# millSensorBoard.net
KiCad netlist of a schematic drawn in EAGLE
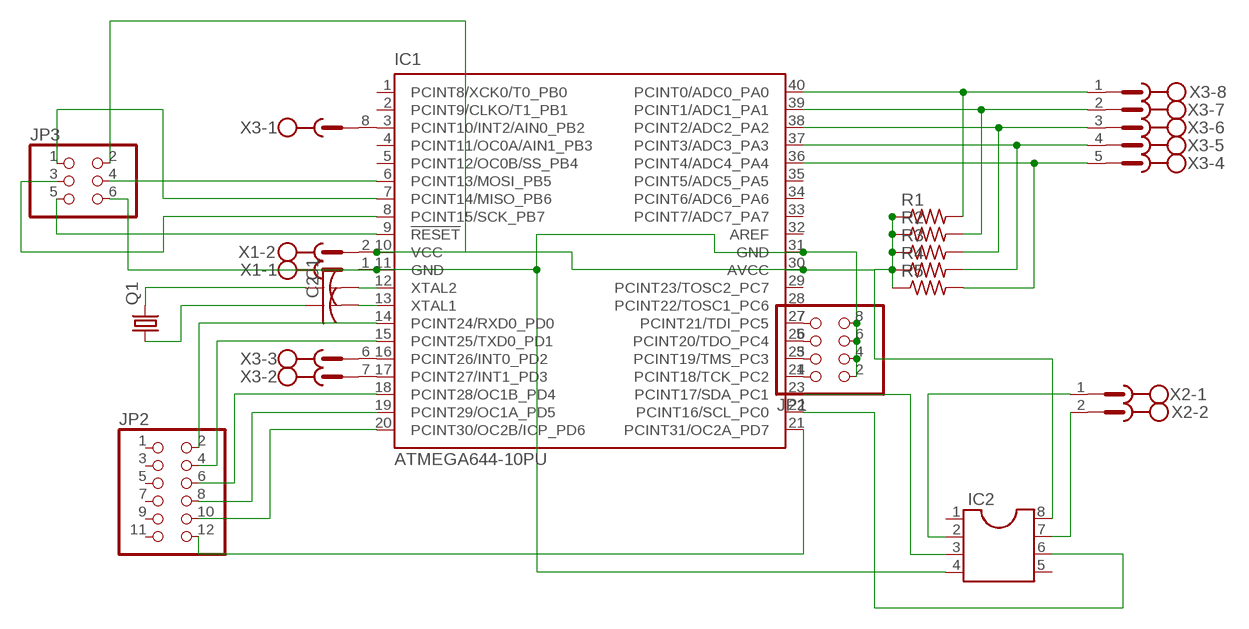
[diagram p0: schematic, sheet 1]

(export (version "E")
  (design (tool "Eeschema 10.0.6"))
  (components
    (comp (ref "C1")
      (value "C-US025-025X050")
      (footprint "eagle-import:C025-025X050")
      (libsource (lib "eagle-import") (part "C-US025-025X050"))
    )
    (comp (ref "C2")
      (value "C-US025-025X050")
      (footprint "eagle-import:C025-025X050")
      (libsource (lib "eagle-import") (part "C-US025-025X050"))
    )
    (comp (ref "IC1")
      (value "ATMEGA644-10PU")
      (footprint "eagle-import:DIL40")
      (fields (field (name "MPN") "ATMEGA644V-10PU"))
      (libsource (lib "eagle-import") (part "ATMEGA644-PU10"))
    )
    (comp (ref "IC2")
      (value "DIL8")
      (footprint "eagle-import:DIL08")
      (libsource (lib "eagle-import") (part "DIL8"))
    )
    (comp (ref "JP1")
      (value "PINHD-2X4")
      (footprint "eagle-import:2X04")
      (libsource (lib "eagle-import") (part "PINHD-2X4"))
    )
    (comp (ref "JP2")
      (value "PINHD-2X6")
      (footprint "eagle-import:2X06")
      (libsource (lib "eagle-import") (part "PINHD-2X6"))
    )
    (comp (ref "JP3")
      (value "PINHD-2X3")
      (footprint "eagle-import:2X03")
      (libsource (lib "eagle-import") (part "PINHD-2X3"))
    )
    (comp (ref "Q1")
      (value "CRYSTALHC49S")
      (footprint "eagle-import:HC49_S")
      (libsource (lib "eagle-import") (part "CRYSTALHC49S"))
    )
    (comp (ref "R1")
      (value "R-US_0207/10")
      (footprint "eagle-import:0207_10")
      (libsource (lib "eagle-import") (part "R-US_0207/10"))
    )
    (comp (ref "R2")
      (value "R-US_0207/10")
      (footprint "eagle-import:0207_10")
      (libsource (lib "eagle-import") (part "R-US_0207/10"))
    )
    (comp (ref "R3")
      (value "R-US_0207/10")
      (footprint "eagle-import:0207_10")
      (libsource (lib "eagle-import") (part "R-US_0207/10"))
    )
    (comp (ref "R4")
      (value "R-US_0207/10")
      (footprint "eagle-import:0207_10")
      (libsource (lib "eagle-import") (part "R-US_0207/10"))
    )
    (comp (ref "R5")
      (value "R-US_0207/10")
      (footprint "eagle-import:0207_10")
      (libsource (lib "eagle-import") (part "R-US_0207/10"))
    )
    (comp (ref "X1")
      (value "MSTBV2")
      (footprint "eagle-import:MSTBV2")
      (libsource (lib "eagle-import") (part "MSTBV2"))
    )
    (comp (ref "X2")
      (value "MSTBV2")
      (footprint "eagle-import:MSTBV2")
      (libsource (lib "eagle-import") (part "MSTBV2"))
    )
    (comp (ref "X3")
      (value "MSTBV8")
      (footprint "eagle-import:MSTBV8")
      (libsource (lib "eagle-import") (part "MSTBV8"))
    )
  )
  (nets
    (net (code "1") (name "Net-(C1-Pad1)") (class "Default")
      (node (ref "C1") (pin "1") (pinfunction "1_1") (pintype "passive"))
      (node (ref "Q1") (pin "2") (pinfunction "2_2") (pintype "passive"))
    )
    (net (code "2") (name "Net-(C2-Pad1)") (class "Default")
      (node (ref "C2") (pin "1") (pinfunction "1_1") (pintype "passive"))
      (node (ref "Q1") (pin "1") (pinfunction "1_1") (pintype "passive"))
    )
    (net (code "3") (name "Net-(IC1-AVCC)") (class "Default")
      (node (ref "IC1") (pin "10") (pinfunction "VCC_10") (pintype "power_in"))
      (node (ref "IC1") (pin "30") (pinfunction "AVCC_30") (pintype "power_in"))
      (node (ref "IC2") (pin "8") (pinfunction "8_8") (pintype "passive"))
      (node (ref "JP3") (pin "2") (pinfunction "2_2") (pintype "passive"))
      (node (ref "R1") (pin "1") (pinfunction "1_1") (pintype "passive"))
      (node (ref "R2") (pin "1") (pinfunction "1_1") (pintype "passive"))
      (node (ref "R3") (pin "1") (pinfunction "1_1") (pintype "passive"))
      (node (ref "R4") (pin "1") (pinfunction "1_1") (pintype "passive"))
      (node (ref "R5") (pin "1") (pinfunction "1_1") (pintype "passive"))
      (node (ref "X1") (pin "2") (pinfunction "SK_2") (pintype "passive"))
    )
    (net (code "4") (name "Net-(IC1-PCINT0{slash}ADC0_PA0)") (class "Default")
      (node (ref "IC1") (pin "40") (pinfunction "PCINT0/ADC0_PA0_40") (pintype "bidirectional"))
      (node (ref "R1") (pin "2") (pinfunction "2_2") (pintype "passive"))
      (node (ref "X3") (pin "1") (pinfunction "SK_1") (pintype "passive"))
    )
    (net (code "5") (name "Net-(IC1-PCINT1{slash}ADC1_PA1)") (class "Default")
      (node (ref "IC1") (pin "39") (pinfunction "PCINT1/ADC1_PA1_39") (pintype "bidirectional"))
      (node (ref "R2") (pin "2") (pinfunction "2_2") (pintype "passive"))
      (node (ref "X3") (pin "2") (pinfunction "SK_2") (pintype "passive"))
    )
    (net (code "6") (name "Net-(IC1-PCINT2{slash}ADC2_PA2)") (class "Default")
      (node (ref "IC1") (pin "38") (pinfunction "PCINT2/ADC2_PA2_38") (pintype "bidirectional"))
      (node (ref "R3") (pin "2") (pinfunction "2_2") (pintype "passive"))
      (node (ref "X3") (pin "3") (pinfunction "SK_3") (pintype "passive"))
    )
    (net (code "7") (name "Net-(IC1-PCINT3{slash}ADC3_PA3)") (class "Default")
      (node (ref "IC1") (pin "37") (pinfunction "PCINT3/ADC3_PA3_37") (pintype "bidirectional"))
      (node (ref "R4") (pin "2") (pinfunction "2_2") (pintype "passive"))
      (node (ref "X3") (pin "4") (pinfunction "SK_4") (pintype "passive"))
    )
    (net (code "8") (name "Net-(IC1-PCINT4{slash}ADC4_PA4)") (class "Default")
      (node (ref "IC1") (pin "36") (pinfunction "PCINT4/ADC4_PA4_36") (pintype "bidirectional"))
      (node (ref "R5") (pin "2") (pinfunction "2_2") (pintype "passive"))
      (node (ref "X3") (pin "5") (pinfunction "SK_5") (pintype "passive"))
    )
    (net (code "9") (name "Net-(IC1-PCINT10{slash}INT2{slash}AIN0_PB2)") (class "Default")
      (node (ref "IC1") (pin "3") (pinfunction "PCINT10/INT2/AIN0_PB2_3") (pintype "bidirectional"))
      (node (ref "X3") (pin "8") (pinfunction "SK_8") (pintype "passive"))
    )
    (net (code "10") (name "Net-(IC1-PCINT13{slash}MOSI_PB5)") (class "Default")
      (node (ref "IC1") (pin "6") (pinfunction "PCINT13/MOSI_PB5_6") (pintype "bidirectional"))
      (node (ref "JP3") (pin "4") (pinfunction "4_4") (pintype "passive"))
    )
    (net (code "11") (name "Net-(IC1-PCINT14{slash}MISO_PB6)") (class "Default")
      (node (ref "IC1") (pin "7") (pinfunction "PCINT14/MISO_PB6_7") (pintype "bidirectional"))
      (node (ref "JP3") (pin "1") (pinfunction "1_1") (pintype "passive"))
    )
    (net (code "12") (name "Net-(IC1-PCINT15{slash}SCK_PB7)") (class "Default")
      (node (ref "IC1") (pin "8") (pinfunction "PCINT15/SCK_PB7_8") (pintype "bidirectional"))
      (node (ref "JP3") (pin "3") (pinfunction "3_3") (pintype "passive"))
    )
    (net (code "13") (name "Net-(IC1-PCINT16{slash}SCL_PC0)") (class "Default")
      (node (ref "IC1") (pin "22") (pinfunction "PCINT16/SCL_PC0_22") (pintype "bidirectional"))
      (node (ref "IC2") (pin "6") (pinfunction "6_6") (pintype "passive"))
    )
    (net (code "14") (name "Net-(IC1-PCINT17{slash}SDA_PC1)") (class "Default")
      (node (ref "IC1") (pin "23") (pinfunction "PCINT17/SDA_PC1_23") (pintype "bidirectional"))
      (node (ref "IC2") (pin "3") (pinfunction "3_3") (pintype "passive"))
    )
    (net (code "15") (name "Net-(IC1-PCINT18{slash}TCK_PC2)") (class "Default")
      (node (ref "IC1") (pin "24") (pinfunction "PCINT18/TCK_PC2_24") (pintype "bidirectional"))
      (node (ref "JP1") (pin "1") (pinfunction "1_1") (pintype "passive"))
    )
    (net (code "16") (name "Net-(IC1-PCINT19{slash}TMS_PC3)") (class "Default")
      (node (ref "IC1") (pin "25") (pinfunction "PCINT19/TMS_PC3_25") (pintype "bidirectional"))
      (node (ref "JP1") (pin "3") (pinfunction "3_3") (pintype "passive"))
    )
    (net (code "17") (name "Net-(IC1-PCINT20{slash}TDO_PC4)") (class "Default")
      (node (ref "IC1") (pin "26") (pinfunction "PCINT20/TDO_PC4_26") (pintype "bidirectional"))
      (node (ref "JP1") (pin "5") (pinfunction "5_5") (pintype "passive"))
    )
    (net (code "18") (name "Net-(IC1-PCINT21{slash}TDI_PC5)") (class "Default")
      (node (ref "IC1") (pin "27") (pinfunction "PCINT21/TDI_PC5_27") (pintype "bidirectional"))
      (node (ref "JP1") (pin "7") (pinfunction "7_7") (pintype "passive"))
    )
    (net (code "19") (name "Net-(IC1-PCINT24{slash}RXD0_PD0)") (class "Default")
      (node (ref "IC1") (pin "14") (pinfunction "PCINT24/RXD0_PD0_14") (pintype "bidirectional"))
      (node (ref "JP2") (pin "2") (pinfunction "2_2") (pintype "passive"))
    )
    (net (code "20") (name "Net-(IC1-PCINT25{slash}TXD0_PD1)") (class "Default")
      (node (ref "IC1") (pin "15") (pinfunction "PCINT25/TXD0_PD1_15") (pintype "bidirectional"))
      (node (ref "JP2") (pin "4") (pinfunction "4_4") (pintype "passive"))
    )
    (net (code "21") (name "Net-(IC1-PCINT26{slash}INT0_PD2)") (class "Default")
      (node (ref "IC1") (pin "16") (pinfunction "PCINT26/INT0_PD2_16") (pintype "bidirectional"))
      (node (ref "X3") (pin "6") (pinfunction "SK_6") (pintype "passive"))
    )
    (net (code "22") (name "Net-(IC1-PCINT27{slash}INT1_PD3)") (class "Default")
      (node (ref "IC1") (pin "17") (pinfunction "PCINT27/INT1_PD3_17") (pintype "bidirectional"))
      (node (ref "X3") (pin "7") (pinfunction "SK_7") (pintype "passive"))
    )
    (net (code "23") (name "Net-(IC1-PCINT28{slash}OC1B_PD4)") (class "Default")
      (node (ref "IC1") (pin "18") (pinfunction "PCINT28/OC1B_PD4_18") (pintype "bidirectional"))
      (node (ref "JP2") (pin "6") (pinfunction "6_6") (pintype "passive"))
    )
    (net (code "24") (name "Net-(IC1-PCINT29{slash}OC1A_PD5)") (class "Default")
      (node (ref "IC1") (pin "19") (pinfunction "PCINT29/OC1A_PD5_19") (pintype "bidirectional"))
      (node (ref "JP2") (pin "8") (pinfunction "8_8") (pintype "passive"))
    )
    (net (code "25") (name "Net-(IC1-PCINT30{slash}OC2B{slash}ICP_PD6)") (class "Default")
      (node (ref "IC1") (pin "20") (pinfunction "PCINT30/OC2B/ICP_PD6_20") (pintype "bidirectional"))
      (node (ref "JP2") (pin "10") (pinfunction "10_10") (pintype "passive"))
    )
    (net (code "26") (name "Net-(IC1-PCINT31{slash}OC2A_PD7)") (class "Default")
      (node (ref "IC1") (pin "21") (pinfunction "PCINT31/OC2A_PD7_21") (pintype "bidirectional"))
      (node (ref "JP2") (pin "12") (pinfunction "12_12") (pintype "passive"))
    )
    (net (code "27") (name "Net-(IC1-XTAL1)") (class "Default")
      (node (ref "C2") (pin "2") (pinfunction "2_2") (pintype "passive"))
      (node (ref "IC1") (pin "13") (pinfunction "XTAL1_13") (pintype "input"))
    )
    (net (code "28") (name "Net-(IC1-XTAL2)") (class "Default")
      (node (ref "C1") (pin "2") (pinfunction "2_2") (pintype "passive"))
      (node (ref "IC1") (pin "12") (pinfunction "XTAL2_12") (pintype "output"))
    )
    (net (code "29") (name "Net-(IC1-~{RESET})") (class "Default")
      (node (ref "IC1") (pin "9") (pinfunction "~{RESET}_9") (pintype "input"))
      (node (ref "JP3") (pin "5") (pinfunction "5_5") (pintype "passive"))
    )
    (net (code "30") (name "Net-(X1A-SK)") (class "Default")
      (node (ref "IC1") (pin "11") (pinfunction "GND_11") (pintype "power_in"))
      (node (ref "IC1") (pin "31") (pinfunction "GND_31") (pintype "power_in"))
      (node (ref "IC2") (pin "4") (pinfunction "4_4") (pintype "passive"))
      (node (ref "JP1") (pin "2") (pinfunction "2_2") (pintype "passive"))
      (node (ref "JP1") (pin "4") (pinfunction "4_4") (pintype "passive"))
      (node (ref "JP1") (pin "6") (pinfunction "6_6") (pintype "passive"))
      (node (ref "JP1") (pin "8") (pinfunction "8_8") (pintype "passive"))
      (node (ref "JP3") (pin "6") (pinfunction "6_6") (pintype "passive"))
      (node (ref "X1") (pin "1") (pinfunction "SK_1") (pintype "passive"))
    )
    (net (code "31") (name "Net-(X2A-SK)") (class "Default")
      (node (ref "IC2") (pin "2") (pinfunction "2_2") (pintype "passive"))
      (node (ref "X2") (pin "1") (pinfunction "SK_1") (pintype "passive"))
    )
    (net (code "32") (name "Net-(X2B-SK)") (class "Default")
      (node (ref "IC2") (pin "7") (pinfunction "7_7") (pintype "passive"))
      (node (ref "X2") (pin "2") (pinfunction "SK_2") (pintype "passive"))
    )
    (net (code "33") (name "unconnected-(IC1-AREF-Pad32)") (class "Default")
      (node (ref "IC1") (pin "32") (pinfunction "AREF_32") (pintype "passive"))
    )
    (net (code "34") (name "unconnected-(IC1-PCINT5{slash}ADC5_PA5-Pad35)") (class "Default")
      (node (ref "IC1") (pin "35") (pinfunction "PCINT5/ADC5_PA5_35") (pintype "bidirectional"))
    )
    (net (code "35") (name "unconnected-(IC1-PCINT6{slash}ADC6_PA6-Pad34)") (class "Default")
      (node (ref "IC1") (pin "34") (pinfunction "PCINT6/ADC6_PA6_34") (pintype "bidirectional"))
    )
    (net (code "36") (name "unconnected-(IC1-PCINT7{slash}ADC7_PA7-Pad33)") (class "Default")
      (node (ref "IC1") (pin "33") (pinfunction "PCINT7/ADC7_PA7_33") (pintype "bidirectional"))
    )
    (net (code "37") (name "unconnected-(IC1-PCINT8{slash}XCK0{slash}T0_PB0-Pad1)") (class "Default")
      (node (ref "IC1") (pin "1") (pinfunction "PCINT8/XCK0/T0_PB0_1") (pintype "bidirectional"))
    )
    (net (code "38") (name "unconnected-(IC1-PCINT9{slash}CLKO{slash}T1_PB1-Pad2)") (class "Default")
      (node (ref "IC1") (pin "2") (pinfunction "PCINT9/CLKO/T1_PB1_2") (pintype "bidirectional"))
    )
    (net (code "39") (name "unconnected-(IC1-PCINT11{slash}OC0A{slash}AIN1_PB3-Pad4)") (class "Default")
      (node (ref "IC1") (pin "4") (pinfunction "PCINT11/OC0A/AIN1_PB3_4") (pintype "bidirectional"))
    )
    (net (code "40") (name "unconnected-(IC1-PCINT12{slash}OC0B{slash}SS_PB4-Pad5)") (class "Default")
      (node (ref "IC1") (pin "5") (pinfunction "PCINT12/OC0B/SS_PB4_5") (pintype "bidirectional"))
    )
    (net (code "41") (name "unconnected-(IC1-PCINT22{slash}TOSC1_PC6-Pad28)") (class "Default")
      (node (ref "IC1") (pin "28") (pinfunction "PCINT22/TOSC1_PC6_28") (pintype "bidirectional"))
    )
    (net (code "42") (name "unconnected-(IC1-PCINT23{slash}TOSC2_PC7-Pad29)") (class "Default")
      (node (ref "IC1") (pin "29") (pinfunction "PCINT23/TOSC2_PC7_29") (pintype "bidirectional"))
    )
    (net (code "43") (name "unconnected-(IC2-Pad1)") (class "Default")
      (node (ref "IC2") (pin "1") (pinfunction "1_1") (pintype "passive"))
    )
    (net (code "44") (name "unconnected-(IC2-Pad5)") (class "Default")
      (node (ref "IC2") (pin "5") (pinfunction "5_5") (pintype "passive"))
    )
    (net (code "45") (name "unconnected-(JP2-Pad1)") (class "Default")
      (node (ref "JP2") (pin "1") (pinfunction "1_1") (pintype "passive"))
    )
    (net (code "46") (name "unconnected-(JP2-Pad3)") (class "Default")
      (node (ref "JP2") (pin "3") (pinfunction "3_3") (pintype "passive"))
    )
    (net (code "47") (name "unconnected-(JP2-Pad5)") (class "Default")
      (node (ref "JP2") (pin "5") (pinfunction "5_5") (pintype "passive"))
    )
    (net (code "48") (name "unconnected-(JP2-Pad7)") (class "Default")
      (node (ref "JP2") (pin "7") (pinfunction "7_7") (pintype "passive"))
    )
    (net (code "49") (name "unconnected-(JP2-Pad9)") (class "Default")
      (node (ref "JP2") (pin "9") (pinfunction "9_9") (pintype "passive"))
    )
    (net (code "50") (name "unconnected-(JP2-Pad11)") (class "Default")
      (node (ref "JP2") (pin "11") (pinfunction "11_11") (pintype "passive"))
    )
  )
)
